# untitled.net
KiCad netlist of a schematic drawn in EAGLE
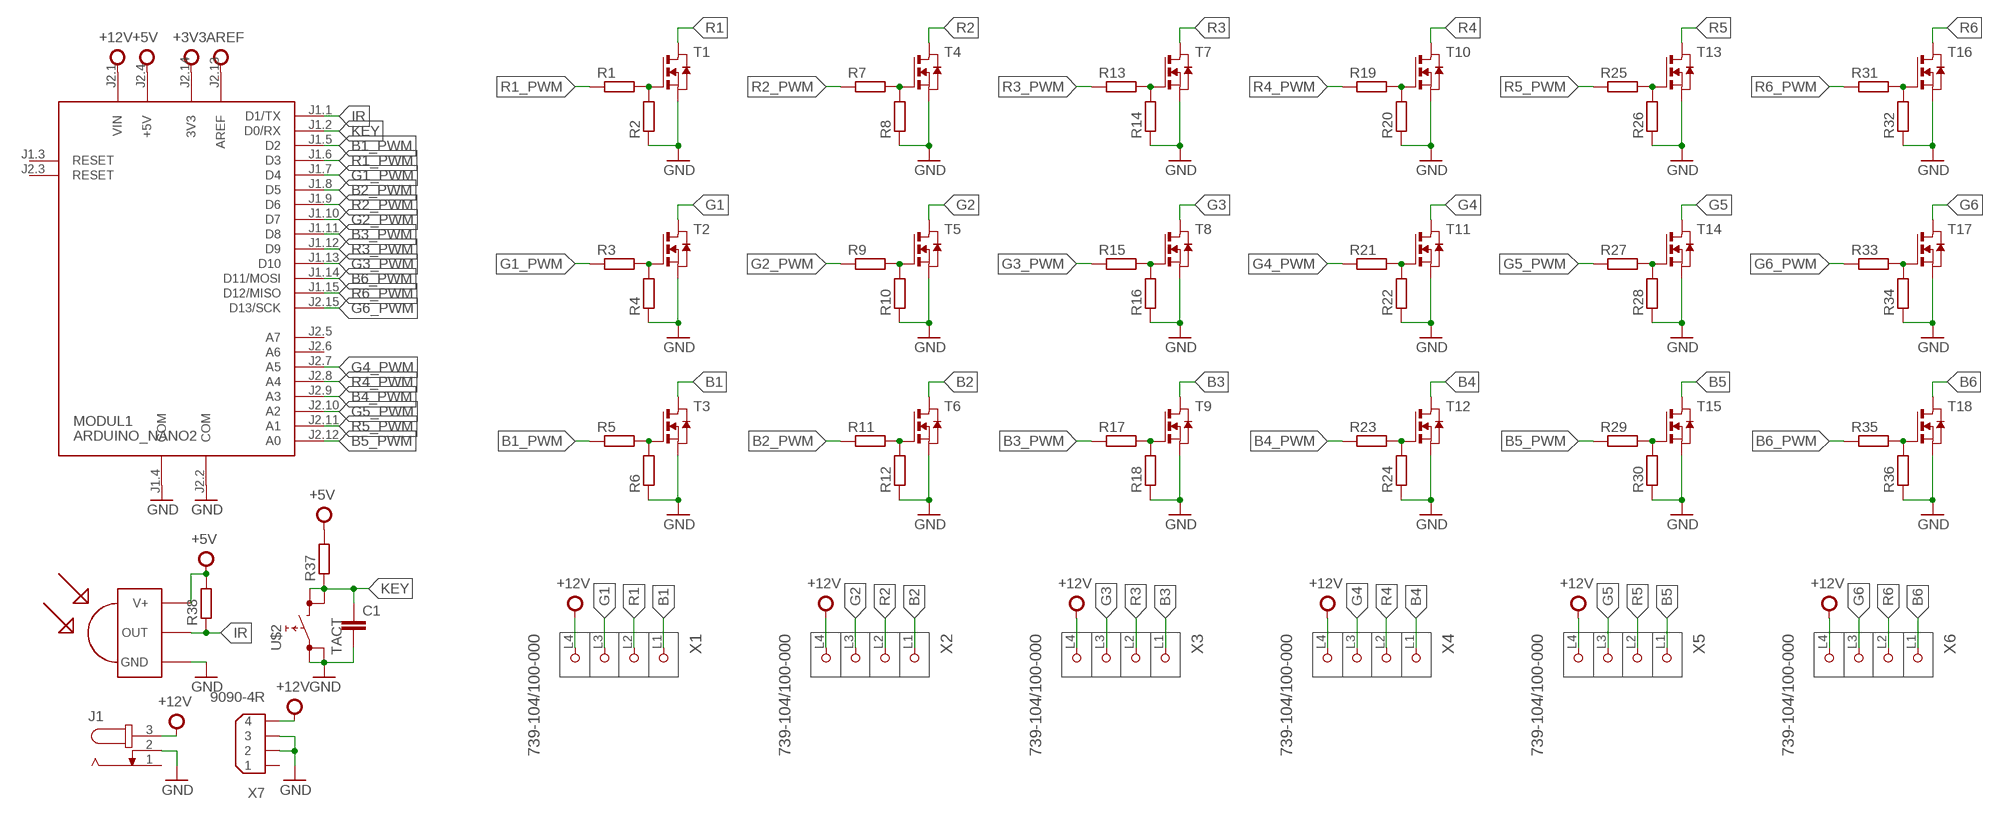
[diagram p0: schematic, sheet 1]

(export (version "E")
  (design (tool "Eeschema 10.0.6"))
  (components
    (comp (ref "C1")
      (value "C-EUC0805")
      (footprint "eagle-import:C0805")
      (libsource (lib "eagle-import") (part "C-EUC0805"))
    )
    (comp (ref "J1")
      (value "JACK-PLUG1")
      (footprint "eagle-import:SPC4078")
      (libsource (lib "eagle-import") (part "JACK-PLUG1"))
    )
    (comp (ref "MODUL1")
      (value "ARDUINO_NANO2")
      (footprint "eagle-import:ARDUINO_NANO2")
      (libsource (lib "eagle-import") (part "ARDUINO_NANO2"))
    )
    (comp (ref "R1")
      (value "R-EU_R0805")
      (footprint "eagle-import:R0805")
      (libsource (lib "eagle-import") (part "R-EU_R0805"))
    )
    (comp (ref "R2")
      (value "R-EU_R0805")
      (footprint "eagle-import:R0805")
      (libsource (lib "eagle-import") (part "R-EU_R0805"))
    )
    (comp (ref "R3")
      (value "R-EU_R0805")
      (footprint "eagle-import:R0805")
      (libsource (lib "eagle-import") (part "R-EU_R0805"))
    )
    (comp (ref "R4")
      (value "R-EU_R0805")
      (footprint "eagle-import:R0805")
      (libsource (lib "eagle-import") (part "R-EU_R0805"))
    )
    (comp (ref "R5")
      (value "R-EU_R0805")
      (footprint "eagle-import:R0805")
      (libsource (lib "eagle-import") (part "R-EU_R0805"))
    )
    (comp (ref "R6")
      (value "R-EU_R0805")
      (footprint "eagle-import:R0805")
      (libsource (lib "eagle-import") (part "R-EU_R0805"))
    )
    (comp (ref "R7")
      (value "R-EU_R0805")
      (footprint "eagle-import:R0805")
      (libsource (lib "eagle-import") (part "R-EU_R0805"))
    )
    (comp (ref "R8")
      (value "R-EU_R0805")
      (footprint "eagle-import:R0805")
      (libsource (lib "eagle-import") (part "R-EU_R0805"))
    )
    (comp (ref "R9")
      (value "R-EU_R0805")
      (footprint "eagle-import:R0805")
      (libsource (lib "eagle-import") (part "R-EU_R0805"))
    )
    (comp (ref "R10")
      (value "R-EU_R0805")
      (footprint "eagle-import:R0805")
      (libsource (lib "eagle-import") (part "R-EU_R0805"))
    )
    (comp (ref "R11")
      (value "R-EU_R0805")
      (footprint "eagle-import:R0805")
      (libsource (lib "eagle-import") (part "R-EU_R0805"))
    )
    (comp (ref "R12")
      (value "R-EU_R0805")
      (footprint "eagle-import:R0805")
      (libsource (lib "eagle-import") (part "R-EU_R0805"))
    )
    (comp (ref "R13")
      (value "R-EU_R0805")
      (footprint "eagle-import:R0805")
      (libsource (lib "eagle-import") (part "R-EU_R0805"))
    )
    (comp (ref "R14")
      (value "R-EU_R0805")
      (footprint "eagle-import:R0805")
      (libsource (lib "eagle-import") (part "R-EU_R0805"))
    )
    (comp (ref "R15")
      (value "R-EU_R0805")
      (footprint "eagle-import:R0805")
      (libsource (lib "eagle-import") (part "R-EU_R0805"))
    )
    (comp (ref "R16")
      (value "R-EU_R0805")
      (footprint "eagle-import:R0805")
      (libsource (lib "eagle-import") (part "R-EU_R0805"))
    )
    (comp (ref "R17")
      (value "R-EU_R0805")
      (footprint "eagle-import:R0805")
      (libsource (lib "eagle-import") (part "R-EU_R0805"))
    )
    (comp (ref "R18")
      (value "R-EU_R0805")
      (footprint "eagle-import:R0805")
      (libsource (lib "eagle-import") (part "R-EU_R0805"))
    )
    (comp (ref "R19")
      (value "R-EU_R0805")
      (footprint "eagle-import:R0805")
      (libsource (lib "eagle-import") (part "R-EU_R0805"))
    )
    (comp (ref "R20")
      (value "R-EU_R0805")
      (footprint "eagle-import:R0805")
      (libsource (lib "eagle-import") (part "R-EU_R0805"))
    )
    (comp (ref "R21")
      (value "R-EU_R0805")
      (footprint "eagle-import:R0805")
      (libsource (lib "eagle-import") (part "R-EU_R0805"))
    )
    (comp (ref "R22")
      (value "R-EU_R0805")
      (footprint "eagle-import:R0805")
      (libsource (lib "eagle-import") (part "R-EU_R0805"))
    )
    (comp (ref "R23")
      (value "R-EU_R0805")
      (footprint "eagle-import:R0805")
      (libsource (lib "eagle-import") (part "R-EU_R0805"))
    )
    (comp (ref "R24")
      (value "R-EU_R0805")
      (footprint "eagle-import:R0805")
      (libsource (lib "eagle-import") (part "R-EU_R0805"))
    )
    (comp (ref "R25")
      (value "R-EU_R0805")
      (footprint "eagle-import:R0805")
      (libsource (lib "eagle-import") (part "R-EU_R0805"))
    )
    (comp (ref "R26")
      (value "R-EU_R0805")
      (footprint "eagle-import:R0805")
      (libsource (lib "eagle-import") (part "R-EU_R0805"))
    )
    (comp (ref "R27")
      (value "R-EU_R0805")
      (footprint "eagle-import:R0805")
      (libsource (lib "eagle-import") (part "R-EU_R0805"))
    )
    (comp (ref "R28")
      (value "R-EU_R0805")
      (footprint "eagle-import:R0805")
      (libsource (lib "eagle-import") (part "R-EU_R0805"))
    )
    (comp (ref "R29")
      (value "R-EU_R0805")
      (footprint "eagle-import:R0805")
      (libsource (lib "eagle-import") (part "R-EU_R0805"))
    )
    (comp (ref "R30")
      (value "R-EU_R0805")
      (footprint "eagle-import:R0805")
      (libsource (lib "eagle-import") (part "R-EU_R0805"))
    )
    (comp (ref "R31")
      (value "R-EU_R0805")
      (footprint "eagle-import:R0805")
      (libsource (lib "eagle-import") (part "R-EU_R0805"))
    )
    (comp (ref "R32")
      (value "R-EU_R0805")
      (footprint "eagle-import:R0805")
      (libsource (lib "eagle-import") (part "R-EU_R0805"))
    )
    (comp (ref "R33")
      (value "R-EU_R0805")
      (footprint "eagle-import:R0805")
      (libsource (lib "eagle-import") (part "R-EU_R0805"))
    )
    (comp (ref "R34")
      (value "R-EU_R0805")
      (footprint "eagle-import:R0805")
      (libsource (lib "eagle-import") (part "R-EU_R0805"))
    )
    (comp (ref "R35")
      (value "R-EU_R0805")
      (footprint "eagle-import:R0805")
      (libsource (lib "eagle-import") (part "R-EU_R0805"))
    )
    (comp (ref "R36")
      (value "R-EU_R0805")
      (footprint "eagle-import:R0805")
      (libsource (lib "eagle-import") (part "R-EU_R0805"))
    )
    (comp (ref "R37")
      (value "R-EU_R0805")
      (footprint "eagle-import:R0805")
      (libsource (lib "eagle-import") (part "R-EU_R0805"))
    )
    (comp (ref "R38")
      (value "R-EU_R0805")
      (footprint "eagle-import:R0805")
      (libsource (lib "eagle-import") (part "R-EU_R0805"))
    )
    (comp (ref "T1")
      (value "NMOSSOT23")
      (footprint "eagle-import:SOT-23")
      (libsource (lib "eagle-import") (part "NMOSSOT23"))
    )
    (comp (ref "T2")
      (value "NMOSSOT23")
      (footprint "eagle-import:SOT-23")
      (libsource (lib "eagle-import") (part "NMOSSOT23"))
    )
    (comp (ref "T3")
      (value "NMOSSOT23")
      (footprint "eagle-import:SOT-23")
      (libsource (lib "eagle-import") (part "NMOSSOT23"))
    )
    (comp (ref "T4")
      (value "NMOSSOT23")
      (footprint "eagle-import:SOT-23")
      (libsource (lib "eagle-import") (part "NMOSSOT23"))
    )
    (comp (ref "T5")
      (value "NMOSSOT23")
      (footprint "eagle-import:SOT-23")
      (libsource (lib "eagle-import") (part "NMOSSOT23"))
    )
    (comp (ref "T6")
      (value "NMOSSOT23")
      (footprint "eagle-import:SOT-23")
      (libsource (lib "eagle-import") (part "NMOSSOT23"))
    )
    (comp (ref "T7")
      (value "NMOSSOT23")
      (footprint "eagle-import:SOT-23")
      (libsource (lib "eagle-import") (part "NMOSSOT23"))
    )
    (comp (ref "T8")
      (value "NMOSSOT23")
      (footprint "eagle-import:SOT-23")
      (libsource (lib "eagle-import") (part "NMOSSOT23"))
    )
    (comp (ref "T9")
      (value "NMOSSOT23")
      (footprint "eagle-import:SOT-23")
      (libsource (lib "eagle-import") (part "NMOSSOT23"))
    )
    (comp (ref "T10")
      (value "NMOSSOT23")
      (footprint "eagle-import:SOT-23")
      (libsource (lib "eagle-import") (part "NMOSSOT23"))
    )
    (comp (ref "T11")
      (value "NMOSSOT23")
      (footprint "eagle-import:SOT-23")
      (libsource (lib "eagle-import") (part "NMOSSOT23"))
    )
    (comp (ref "T12")
      (value "NMOSSOT23")
      (footprint "eagle-import:SOT-23")
      (libsource (lib "eagle-import") (part "NMOSSOT23"))
    )
    (comp (ref "T13")
      (value "NMOSSOT23")
      (footprint "eagle-import:SOT-23")
      (libsource (lib "eagle-import") (part "NMOSSOT23"))
    )
    (comp (ref "T14")
      (value "NMOSSOT23")
      (footprint "eagle-import:SOT-23")
      (libsource (lib "eagle-import") (part "NMOSSOT23"))
    )
    (comp (ref "T15")
      (value "NMOSSOT23")
      (footprint "eagle-import:SOT-23")
      (libsource (lib "eagle-import") (part "NMOSSOT23"))
    )
    (comp (ref "T16")
      (value "NMOSSOT23")
      (footprint "eagle-import:SOT-23")
      (libsource (lib "eagle-import") (part "NMOSSOT23"))
    )
    (comp (ref "T17")
      (value "NMOSSOT23")
      (footprint "eagle-import:SOT-23")
      (libsource (lib "eagle-import") (part "NMOSSOT23"))
    )
    (comp (ref "T18")
      (value "NMOSSOT23")
      (footprint "eagle-import:SOT-23")
      (libsource (lib "eagle-import") (part "NMOSSOT23"))
    )
    (comp (ref "U$1")
      (value "TSOP1738")
      (footprint "eagle-import:TSOP17XX")
      (libsource (lib "eagle-import") (part "TSOP1738"))
    )
    (comp (ref "U$2")
      (value "TACT")
      (footprint "eagle-import:TL1105")
      (libsource (lib "eagle-import") (part "TACT"))
    )
    (comp (ref "X1")
      (value "739-104/100-000")
      (footprint "eagle-import:P-739-104_100-000")
      (libsource (lib "eagle-import") (part "739-104/100-000"))
    )
    (comp (ref "X2")
      (value "739-104/100-000")
      (footprint "eagle-import:P-739-104_100-000")
      (libsource (lib "eagle-import") (part "739-104/100-000"))
    )
    (comp (ref "X3")
      (value "739-104/100-000")
      (footprint "eagle-import:P-739-104_100-000")
      (libsource (lib "eagle-import") (part "739-104/100-000"))
    )
    (comp (ref "X4")
      (value "739-104/100-000")
      (footprint "eagle-import:P-739-104_100-000")
      (libsource (lib "eagle-import") (part "739-104/100-000"))
    )
    (comp (ref "X5")
      (value "739-104/100-000")
      (footprint "eagle-import:P-739-104_100-000")
      (libsource (lib "eagle-import") (part "739-104/100-000"))
    )
    (comp (ref "X6")
      (value "739-104/100-000")
      (footprint "eagle-import:P-739-104_100-000")
      (libsource (lib "eagle-import") (part "739-104/100-000"))
    )
    (comp (ref "X7")
      (value "9090-4R")
      (footprint "eagle-import:9090-4R")
      (libsource (lib "eagle-import") (part "9090-4R"))
    )
  )
  (nets
    (net (code "1") (name "+3V3") (class "Default")
      (node (ref "MODUL1") (pin "J2.14") (pinfunction "3V3_J2.14") (pintype "power_in"))
    )
    (net (code "2") (name "+5V") (class "Default")
      (node (ref "MODUL1") (pin "J2.4") (pinfunction "+5V_J2.4") (pintype "power_in"))
      (node (ref "R37") (pin "2") (pinfunction "2_2") (pintype "passive"))
      (node (ref "R38") (pin "2") (pinfunction "2_2") (pintype "passive"))
      (node (ref "U$1") (pin "V+") (pinfunction "V+_V+") (pintype "bidirectional"))
    )
    (net (code "3") (name "+12V") (class "Default")
      (node (ref "J1") (pin "3") (pinfunction "3_3") (pintype "passive"))
      (node (ref "MODUL1") (pin "J2.1") (pinfunction "VIN_J2.1") (pintype "power_in"))
      (node (ref "X1") (pin "L4") (pinfunction "P4_L4") (pintype "bidirectional"))
      (node (ref "X2") (pin "L4") (pinfunction "P4_L4") (pintype "bidirectional"))
      (node (ref "X3") (pin "L4") (pinfunction "P4_L4") (pintype "bidirectional"))
      (node (ref "X4") (pin "L4") (pinfunction "P4_L4") (pintype "bidirectional"))
      (node (ref "X5") (pin "L4") (pinfunction "P4_L4") (pintype "bidirectional"))
      (node (ref "X6") (pin "L4") (pinfunction "P4_L4") (pintype "bidirectional"))
      (node (ref "X7") (pin "4") (pinfunction "4_4") (pintype "passive"))
    )
    (net (code "4") (name "AREF") (class "Default")
      (node (ref "MODUL1") (pin "J2.13") (pinfunction "AREF_J2.13") (pintype "power_in"))
    )
    (net (code "5") (name "B1") (class "Default")
      (node (ref "T3") (pin "1") (pinfunction "D_1") (pintype "passive"))
      (node (ref "X1") (pin "L1") (pinfunction "P1_L1") (pintype "bidirectional"))
    )
    (net (code "6") (name "B1_PWM") (class "Default")
      (node (ref "MODUL1") (pin "J1.5") (pinfunction "D2_J1.5") (pintype "bidirectional"))
      (node (ref "R5") (pin "1") (pinfunction "1_1") (pintype "passive"))
    )
    (net (code "7") (name "B2") (class "Default")
      (node (ref "T6") (pin "1") (pinfunction "D_1") (pintype "passive"))
      (node (ref "X2") (pin "L1") (pinfunction "P1_L1") (pintype "bidirectional"))
    )
    (net (code "8") (name "B2_PWM") (class "Default")
      (node (ref "MODUL1") (pin "J1.8") (pinfunction "D5_J1.8") (pintype "bidirectional"))
      (node (ref "R11") (pin "1") (pinfunction "1_1") (pintype "passive"))
    )
    (net (code "9") (name "B3") (class "Default")
      (node (ref "T9") (pin "1") (pinfunction "D_1") (pintype "passive"))
      (node (ref "X3") (pin "L1") (pinfunction "P1_L1") (pintype "bidirectional"))
    )
    (net (code "10") (name "B3_PWM") (class "Default")
      (node (ref "MODUL1") (pin "J1.11") (pinfunction "D8_J1.11") (pintype "bidirectional"))
      (node (ref "R17") (pin "1") (pinfunction "1_1") (pintype "passive"))
    )
    (net (code "11") (name "B4") (class "Default")
      (node (ref "T12") (pin "1") (pinfunction "D_1") (pintype "passive"))
      (node (ref "X4") (pin "L1") (pinfunction "P1_L1") (pintype "bidirectional"))
    )
    (net (code "12") (name "B4_PWM") (class "Default")
      (node (ref "MODUL1") (pin "J2.9") (pinfunction "A3_J2.9") (pintype "bidirectional"))
      (node (ref "R23") (pin "1") (pinfunction "1_1") (pintype "passive"))
    )
    (net (code "13") (name "B5") (class "Default")
      (node (ref "T15") (pin "1") (pinfunction "D_1") (pintype "passive"))
      (node (ref "X5") (pin "L1") (pinfunction "P1_L1") (pintype "bidirectional"))
    )
    (net (code "14") (name "B5_PWM") (class "Default")
      (node (ref "MODUL1") (pin "J2.12") (pinfunction "A0_J2.12") (pintype "bidirectional"))
      (node (ref "R29") (pin "1") (pinfunction "1_1") (pintype "passive"))
    )
    (net (code "15") (name "B6") (class "Default")
      (node (ref "T18") (pin "1") (pinfunction "D_1") (pintype "passive"))
      (node (ref "X6") (pin "L1") (pinfunction "P1_L1") (pintype "bidirectional"))
    )
    (net (code "16") (name "B6_PWM") (class "Default")
      (node (ref "MODUL1") (pin "J1.14") (pinfunction "D11/MOSI_J1.14") (pintype "bidirectional"))
      (node (ref "R35") (pin "1") (pinfunction "1_1") (pintype "passive"))
    )
    (net (code "17") (name "G1") (class "Default")
      (node (ref "T2") (pin "1") (pinfunction "D_1") (pintype "passive"))
      (node (ref "X1") (pin "L3") (pinfunction "P3_L3") (pintype "bidirectional"))
    )
    (net (code "18") (name "G1_PWM") (class "Default")
      (node (ref "MODUL1") (pin "J1.7") (pinfunction "D4_J1.7") (pintype "bidirectional"))
      (node (ref "R3") (pin "1") (pinfunction "1_1") (pintype "passive"))
    )
    (net (code "19") (name "G2") (class "Default")
      (node (ref "T5") (pin "1") (pinfunction "D_1") (pintype "passive"))
      (node (ref "X2") (pin "L3") (pinfunction "P3_L3") (pintype "bidirectional"))
    )
    (net (code "20") (name "G2_PWM") (class "Default")
      (node (ref "MODUL1") (pin "J1.10") (pinfunction "D7_J1.10") (pintype "bidirectional"))
      (node (ref "R9") (pin "1") (pinfunction "1_1") (pintype "passive"))
    )
    (net (code "21") (name "G3") (class "Default")
      (node (ref "T8") (pin "1") (pinfunction "D_1") (pintype "passive"))
      (node (ref "X3") (pin "L3") (pinfunction "P3_L3") (pintype "bidirectional"))
    )
    (net (code "22") (name "G3_PWM") (class "Default")
      (node (ref "MODUL1") (pin "J1.13") (pinfunction "D10_J1.13") (pintype "bidirectional"))
      (node (ref "R15") (pin "1") (pinfunction "1_1") (pintype "passive"))
    )
    (net (code "23") (name "G4") (class "Default")
      (node (ref "T11") (pin "1") (pinfunction "D_1") (pintype "passive"))
      (node (ref "X4") (pin "L3") (pinfunction "P3_L3") (pintype "bidirectional"))
    )
    (net (code "24") (name "G4_PWM") (class "Default")
      (node (ref "MODUL1") (pin "J2.7") (pinfunction "A5_J2.7") (pintype "bidirectional"))
      (node (ref "R21") (pin "1") (pinfunction "1_1") (pintype "passive"))
    )
    (net (code "25") (name "G5") (class "Default")
      (node (ref "T14") (pin "1") (pinfunction "D_1") (pintype "passive"))
      (node (ref "X5") (pin "L3") (pinfunction "P3_L3") (pintype "bidirectional"))
    )
    (net (code "26") (name "G5_PWM") (class "Default")
      (node (ref "MODUL1") (pin "J2.10") (pinfunction "A2_J2.10") (pintype "bidirectional"))
      (node (ref "R27") (pin "1") (pinfunction "1_1") (pintype "passive"))
    )
    (net (code "27") (name "G6") (class "Default")
      (node (ref "T17") (pin "1") (pinfunction "D_1") (pintype "passive"))
      (node (ref "X6") (pin "L3") (pinfunction "P3_L3") (pintype "bidirectional"))
    )
    (net (code "28") (name "G6_PWM") (class "Default")
      (node (ref "MODUL1") (pin "J2.15") (pinfunction "D13/SCK_J2.15") (pintype "bidirectional"))
      (node (ref "R33") (pin "1") (pinfunction "1_1") (pintype "passive"))
    )
    (net (code "29") (name "GND") (class "Default")
      (node (ref "C1") (pin "2") (pinfunction "2_2") (pintype "passive"))
      (node (ref "J1") (pin "2") (pinfunction "2_2") (pintype "passive"))
      (node (ref "MODUL1") (pin "J1.4") (pinfunction "COM_J1.4") (pintype "power_in"))
      (node (ref "MODUL1") (pin "J2.2") (pinfunction "COM_J2.2") (pintype "power_in"))
      (node (ref "R10") (pin "1") (pinfunction "1_1") (pintype "passive"))
      (node (ref "R12") (pin "1") (pinfunction "1_1") (pintype "passive"))
      (node (ref "R14") (pin "1") (pinfunction "1_1") (pintype "passive"))
      (node (ref "R16") (pin "1") (pinfunction "1_1") (pintype "passive"))
      (node (ref "R18") (pin "1") (pinfunction "1_1") (pintype "passive"))
      (node (ref "R2") (pin "1") (pinfunction "1_1") (pintype "passive"))
      (node (ref "R20") (pin "1") (pinfunction "1_1") (pintype "passive"))
      (node (ref "R22") (pin "1") (pinfunction "1_1") (pintype "passive"))
      (node (ref "R24") (pin "1") (pinfunction "1_1") (pintype "passive"))
      (node (ref "R26") (pin "1") (pinfunction "1_1") (pintype "passive"))
      (node (ref "R28") (pin "1") (pinfunction "1_1") (pintype "passive"))
      (node (ref "R30") (pin "1") (pinfunction "1_1") (pintype "passive"))
      (node (ref "R32") (pin "1") (pinfunction "1_1") (pintype "passive"))
      (node (ref "R34") (pin "1") (pinfunction "1_1") (pintype "passive"))
      (node (ref "R36") (pin "1") (pinfunction "1_1") (pintype "passive"))
      (node (ref "R4") (pin "1") (pinfunction "1_1") (pintype "passive"))
      (node (ref "R6") (pin "1") (pinfunction "1_1") (pintype "passive"))
      (node (ref "R8") (pin "1") (pinfunction "1_1") (pintype "passive"))
      (node (ref "T1") (pin "2") (pinfunction "S_2") (pintype "passive"))
      (node (ref "T10") (pin "2") (pinfunction "S_2") (pintype "passive"))
      (node (ref "T11") (pin "2") (pinfunction "S_2") (pintype "passive"))
      (node (ref "T12") (pin "2") (pinfunction "S_2") (pintype "passive"))
      (node (ref "T13") (pin "2") (pinfunction "S_2") (pintype "passive"))
      (node (ref "T14") (pin "2") (pinfunction "S_2") (pintype "passive"))
      (node (ref "T15") (pin "2") (pinfunction "S_2") (pintype "passive"))
      (node (ref "T16") (pin "2") (pinfunction "S_2") (pintype "passive"))
      (node (ref "T17") (pin "2") (pinfunction "S_2") (pintype "passive"))
      (node (ref "T18") (pin "2") (pinfunction "S_2") (pintype "passive"))
      (node (ref "T2") (pin "2") (pinfunction "S_2") (pintype "passive"))
      (node (ref "T3") (pin "2") (pinfunction "S_2") (pintype "passive"))
      (node (ref "T4") (pin "2") (pinfunction "S_2") (pintype "passive"))
      (node (ref "T5") (pin "2") (pinfunction "S_2") (pintype "passive"))
      (node (ref "T6") (pin "2") (pinfunction "S_2") (pintype "passive"))
      (node (ref "T7") (pin "2") (pinfunction "S_2") (pintype "passive"))
      (node (ref "T8") (pin "2") (pinfunction "S_2") (pintype "passive"))
      (node (ref "T9") (pin "2") (pinfunction "S_2") (pintype "passive"))
      (node (ref "U$1") (pin "GND") (pinfunction "GND_GND") (pintype "bidirectional"))
      (node (ref "U$2") (pin "1") (pinfunction "0_1") (pintype "passive"))
      (node (ref "U$2") (pin "3") (pinfunction "0_3") (pintype "passive"))
      (node (ref "X7") (pin "2") (pinfunction "2_2") (pintype "passive"))
      (node (ref "X7") (pin "3") (pinfunction "3_3") (pintype "passive"))
    )
    (net (code "30") (name "IR") (class "Default")
      (node (ref "MODUL1") (pin "J1.1") (pinfunction "D1/TX_J1.1") (pintype "bidirectional"))
      (node (ref "R38") (pin "1") (pinfunction "1_1") (pintype "passive"))
      (node (ref "U$1") (pin "OUT") (pinfunction "OUT_OUT") (pintype "bidirectional"))
    )
    (net (code "31") (name "KEY") (class "Default")
      (node (ref "C1") (pin "1") (pinfunction "1_1") (pintype "passive"))
      (node (ref "MODUL1") (pin "J1.2") (pinfunction "D0/RX_J1.2") (pintype "bidirectional"))
      (node (ref "R37") (pin "1") (pinfunction "1_1") (pintype "passive"))
      (node (ref "U$2") (pin "2") (pinfunction "1_2") (pintype "passive"))
      (node (ref "U$2") (pin "4") (pinfunction "1_4") (pintype "passive"))
    )
    (net (code "32") (name "Net-(T1-G)") (class "Default")
      (node (ref "R1") (pin "2") (pinfunction "2_2") (pintype "passive"))
      (node (ref "R2") (pin "2") (pinfunction "2_2") (pintype "passive"))
      (node (ref "T1") (pin "3") (pinfunction "G_3") (pintype "passive"))
    )
    (net (code "33") (name "Net-(T2-G)") (class "Default")
      (node (ref "R3") (pin "2") (pinfunction "2_2") (pintype "passive"))
      (node (ref "R4") (pin "2") (pinfunction "2_2") (pintype "passive"))
      (node (ref "T2") (pin "3") (pinfunction "G_3") (pintype "passive"))
    )
    (net (code "34") (name "Net-(T3-G)") (class "Default")
      (node (ref "R5") (pin "2") (pinfunction "2_2") (pintype "passive"))
      (node (ref "R6") (pin "2") (pinfunction "2_2") (pintype "passive"))
      (node (ref "T3") (pin "3") (pinfunction "G_3") (pintype "passive"))
    )
    (net (code "35") (name "Net-(T4-G)") (class "Default")
      (node (ref "R7") (pin "2") (pinfunction "2_2") (pintype "passive"))
      (node (ref "R8") (pin "2") (pinfunction "2_2") (pintype "passive"))
      (node (ref "T4") (pin "3") (pinfunction "G_3") (pintype "passive"))
    )
    (net (code "36") (name "Net-(T5-G)") (class "Default")
      (node (ref "R10") (pin "2") (pinfunction "2_2") (pintype "passive"))
      (node (ref "R9") (pin "2") (pinfunction "2_2") (pintype "passive"))
      (node (ref "T5") (pin "3") (pinfunction "G_3") (pintype "passive"))
    )
    (net (code "37") (name "Net-(T6-G)") (class "Default")
      (node (ref "R11") (pin "2") (pinfunction "2_2") (pintype "passive"))
      (node (ref "R12") (pin "2") (pinfunction "2_2") (pintype "passive"))
      (node (ref "T6") (pin "3") (pinfunction "G_3") (pintype "passive"))
    )
    (net (code "38") (name "Net-(T7-G)") (class "Default")
      (node (ref "R13") (pin "2") (pinfunction "2_2") (pintype "passive"))
      (node (ref "R14") (pin "2") (pinfunction "2_2") (pintype "passive"))
      (node (ref "T7") (pin "3") (pinfunction "G_3") (pintype "passive"))
    )
    (net (code "39") (name "Net-(T8-G)") (class "Default")
      (node (ref "R15") (pin "2") (pinfunction "2_2") (pintype "passive"))
      (node (ref "R16") (pin "2") (pinfunction "2_2") (pintype "passive"))
      (node (ref "T8") (pin "3") (pinfunction "G_3") (pintype "passive"))
    )
    (net (code "40") (name "Net-(T9-G)") (class "Default")
      (node (ref "R17") (pin "2") (pinfunction "2_2") (pintype "passive"))
      (node (ref "R18") (pin "2") (pinfunction "2_2") (pintype "passive"))
      (node (ref "T9") (pin "3") (pinfunction "G_3") (pintype "passive"))
    )
    (net (code "41") (name "Net-(T10-G)") (class "Default")
      (node (ref "R19") (pin "2") (pinfunction "2_2") (pintype "passive"))
      (node (ref "R20") (pin "2") (pinfunction "2_2") (pintype "passive"))
      (node (ref "T10") (pin "3") (pinfunction "G_3") (pintype "passive"))
    )
    (net (code "42") (name "Net-(T11-G)") (class "Default")
      (node (ref "R21") (pin "2") (pinfunction "2_2") (pintype "passive"))
      (node (ref "R22") (pin "2") (pinfunction "2_2") (pintype "passive"))
      (node (ref "T11") (pin "3") (pinfunction "G_3") (pintype "passive"))
    )
    (net (code "43") (name "Net-(T12-G)") (class "Default")
      (node (ref "R23") (pin "2") (pinfunction "2_2") (pintype "passive"))
      (node (ref "R24") (pin "2") (pinfunction "2_2") (pintype "passive"))
      (node (ref "T12") (pin "3") (pinfunction "G_3") (pintype "passive"))
    )
    (net (code "44") (name "Net-(T13-G)") (class "Default")
      (node (ref "R25") (pin "2") (pinfunction "2_2") (pintype "passive"))
      (node (ref "R26") (pin "2") (pinfunction "2_2") (pintype "passive"))
      (node (ref "T13") (pin "3") (pinfunction "G_3") (pintype "passive"))
    )
    (net (code "45") (name "Net-(T14-G)") (class "Default")
      (node (ref "R27") (pin "2") (pinfunction "2_2") (pintype "passive"))
      (node (ref "R28") (pin "2") (pinfunction "2_2") (pintype "passive"))
      (node (ref "T14") (pin "3") (pinfunction "G_3") (pintype "passive"))
    )
    (net (code "46") (name "Net-(T15-G)") (class "Default")
      (node (ref "R29") (pin "2") (pinfunction "2_2") (pintype "passive"))
      (node (ref "R30") (pin "2") (pinfunction "2_2") (pintype "passive"))
      (node (ref "T15") (pin "3") (pinfunction "G_3") (pintype "passive"))
    )
    (net (code "47") (name "Net-(T16-G)") (class "Default")
      (node (ref "R31") (pin "2") (pinfunction "2_2") (pintype "passive"))
      (node (ref "R32") (pin "2") (pinfunction "2_2") (pintype "passive"))
      (node (ref "T16") (pin "3") (pinfunction "G_3") (pintype "passive"))
    )
    (net (code "48") (name "Net-(T17-G)") (class "Default")
      (node (ref "R33") (pin "2") (pinfunction "2_2") (pintype "passive"))
      (node (ref "R34") (pin "2") (pinfunction "2_2") (pintype "passive"))
      (node (ref "T17") (pin "3") (pinfunction "G_3") (pintype "passive"))
    )
    (net (code "49") (name "Net-(T18-G)") (class "Default")
      (node (ref "R35") (pin "2") (pinfunction "2_2") (pintype "passive"))
      (node (ref "R36") (pin "2") (pinfunction "2_2") (pintype "passive"))
      (node (ref "T18") (pin "3") (pinfunction "G_3") (pintype "passive"))
    )
    (net (code "50") (name "R1") (class "Default")
      (node (ref "T1") (pin "1") (pinfunction "D_1") (pintype "passive"))
      (node (ref "X1") (pin "L2") (pinfunction "P2_L2") (pintype "bidirectional"))
    )
    (net (code "51") (name "R1_PWM") (class "Default")
      (node (ref "MODUL1") (pin "J1.6") (pinfunction "D3_J1.6") (pintype "bidirectional"))
      (node (ref "R1") (pin "1") (pinfunction "1_1") (pintype "passive"))
    )
    (net (code "52") (name "R2") (class "Default")
      (node (ref "T4") (pin "1") (pinfunction "D_1") (pintype "passive"))
      (node (ref "X2") (pin "L2") (pinfunction "P2_L2") (pintype "bidirectional"))
    )
    (net (code "53") (name "R2_PWM") (class "Default")
      (node (ref "MODUL1") (pin "J1.9") (pinfunction "D6_J1.9") (pintype "bidirectional"))
      (node (ref "R7") (pin "1") (pinfunction "1_1") (pintype "passive"))
    )
    (net (code "54") (name "R3") (class "Default")
      (node (ref "T7") (pin "1") (pinfunction "D_1") (pintype "passive"))
      (node (ref "X3") (pin "L2") (pinfunction "P2_L2") (pintype "bidirectional"))
    )
    (net (code "55") (name "R3_PWM") (class "Default")
      (node (ref "MODUL1") (pin "J1.12") (pinfunction "D9_J1.12") (pintype "bidirectional"))
      (node (ref "R13") (pin "1") (pinfunction "1_1") (pintype "passive"))
    )
    (net (code "56") (name "R4") (class "Default")
      (node (ref "T10") (pin "1") (pinfunction "D_1") (pintype "passive"))
      (node (ref "X4") (pin "L2") (pinfunction "P2_L2") (pintype "bidirectional"))
    )
    (net (code "57") (name "R4_PWM") (class "Default")
      (node (ref "MODUL1") (pin "J2.8") (pinfunction "A4_J2.8") (pintype "bidirectional"))
      (node (ref "R19") (pin "1") (pinfunction "1_1") (pintype "passive"))
    )
    (net (code "58") (name "R5") (class "Default")
      (node (ref "T13") (pin "1") (pinfunction "D_1") (pintype "passive"))
      (node (ref "X5") (pin "L2") (pinfunction "P2_L2") (pintype "bidirectional"))
    )
    (net (code "59") (name "R5_PWM") (class "Default")
      (node (ref "MODUL1") (pin "J2.11") (pinfunction "A1_J2.11") (pintype "bidirectional"))
      (node (ref "R25") (pin "1") (pinfunction "1_1") (pintype "passive"))
    )
    (net (code "60") (name "R6") (class "Default")
      (node (ref "T16") (pin "1") (pinfunction "D_1") (pintype "passive"))
      (node (ref "X6") (pin "L2") (pinfunction "P2_L2") (pintype "bidirectional"))
    )
    (net (code "61") (name "R6_PWM") (class "Default")
      (node (ref "MODUL1") (pin "J1.15") (pinfunction "D12/MISO_J1.15") (pintype "bidirectional"))
      (node (ref "R31") (pin "1") (pinfunction "1_1") (pintype "passive"))
    )
    (net (code "62") (name "unconnected-(J1-Pad1)") (class "Default")
      (node (ref "J1") (pin "1") (pinfunction "1_1") (pintype "passive"))
    )
    (net (code "63") (name "unconnected-(MODUL1-A6-PadJ2.6)") (class "Default")
      (node (ref "MODUL1") (pin "J2.6") (pinfunction "A6_J2.6") (pintype "bidirectional"))
    )
    (net (code "64") (name "unconnected-(MODUL1-A7-PadJ2.5)") (class "Default")
      (node (ref "MODUL1") (pin "J2.5") (pinfunction "A7_J2.5") (pintype "bidirectional"))
    )
    (net (code "65") (name "unconnected-(MODUL1-RESET-PadJ1.3)") (class "Default")
      (node (ref "MODUL1") (pin "J1.3") (pinfunction "RESET_J1.3") (pintype "bidirectional"))
    )
    (net (code "66") (name "unconnected-(MODUL1-RESET-PadJ2.3)") (class "Default")
      (node (ref "MODUL1") (pin "J2.3") (pinfunction "RESET_J2.3") (pintype "bidirectional"))
    )
    (net (code "67") (name "unconnected-(X7-Pad1)") (class "Default")
      (node (ref "X7") (pin "1") (pinfunction "1_1") (pintype "passive"))
    )
  )
)
